# PowerSupply.net
KiCad netlist of a schematic drawn in Altium Designer
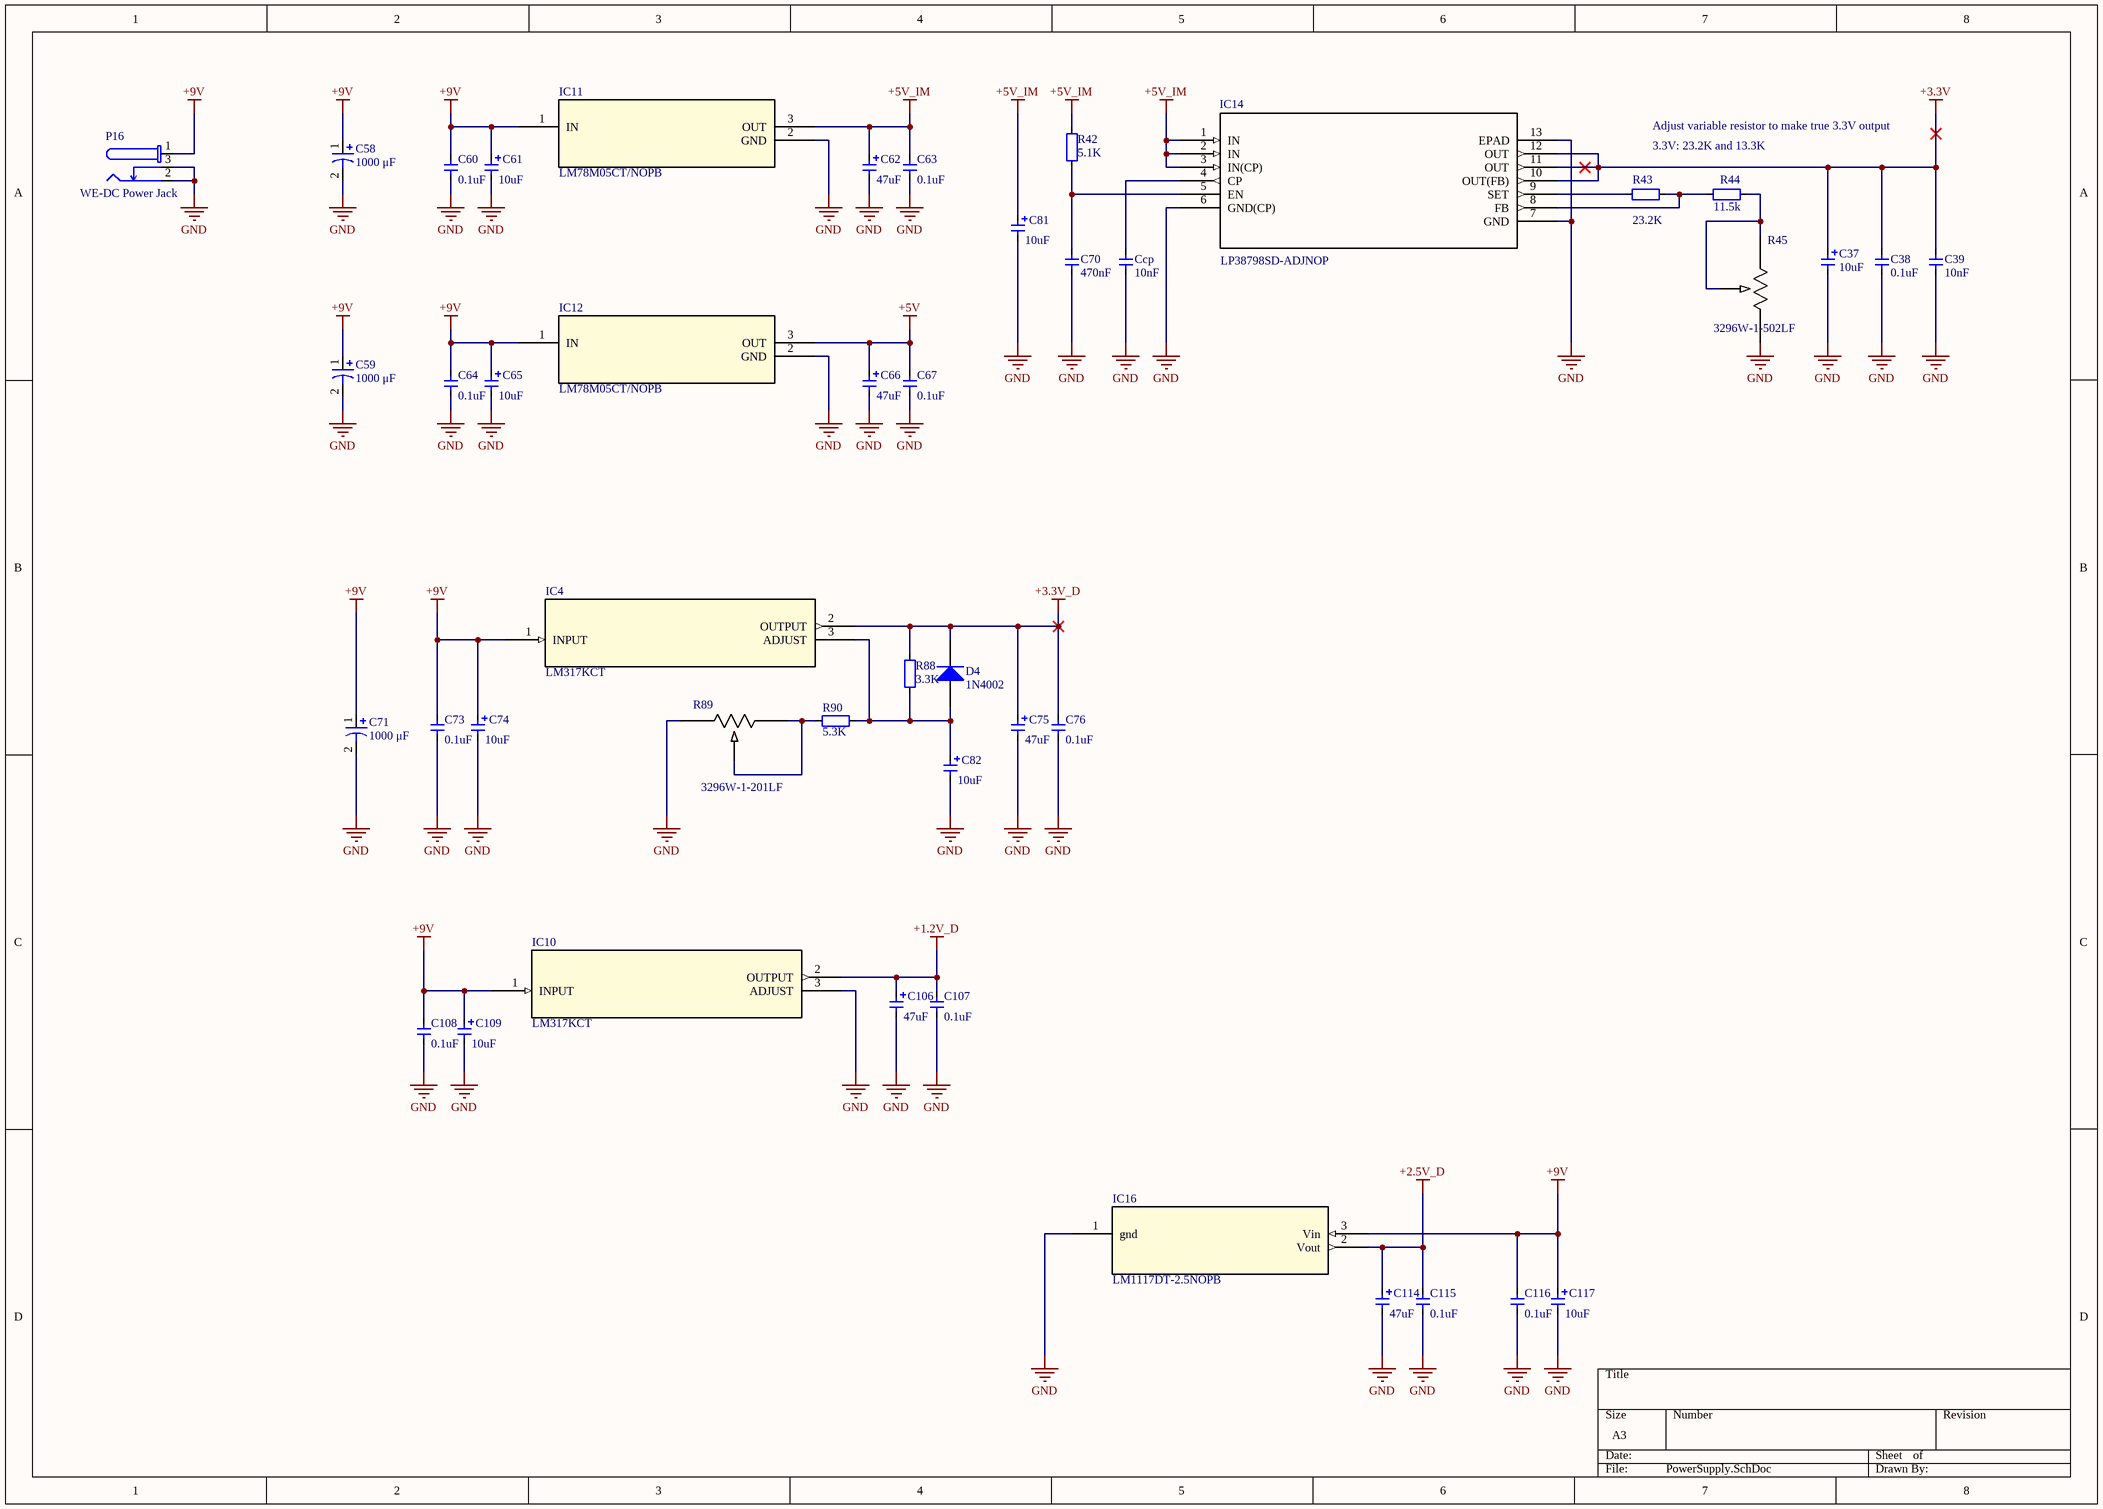
[diagram p0: PowerSupply.SchDoc]

(export (version "E")
  (design (tool "Eeschema 10.0.6"))
  (components
    (comp (ref "C37")
      (value "10uF")
      (footprint "PCB_PassiveCap:CAP_TAN_A1206")
      (description "Capacitor")
      (fields (field (name "Comment") "Cap_Tan_1206"))
      (libsource (lib "SCH_Passive") (part "Cap_Tan_1206"))
    )
    (comp (ref "C38")
      (value "0.1uF")
      (footprint "PCB_PassiveCap:CAP_0603")
      (description "Capacitor")
      (fields (field (name "Comment") "Cap_0603"))
      (libsource (lib "SCH_Passive") (part "Cap_0603"))
    )
    (comp (ref "C39")
      (value "10nF")
      (footprint "PCB_PassiveCap:CAP_0603")
      (description "Capacitor")
      (fields (field (name "Comment") "Cap_0603"))
      (libsource (lib "SCH_Passive") (part "Cap_0603"))
    )
    (comp (ref "C58")
      (value "1000 μF")
      (footprint "WCAP-ATUL 5x11x2x0.5")
      (description "WCAP-ATUL Aluminum Electrolytic Capacitors , 100 μF; + / - 20%; 10 V , 5 x 11")
      (fields
        (field (name "MANUFACTURER") "Wurth Elektronik")
        (field (name "PARTNO") "860040272001")
        (field (name "E-MAIL") "libraries@we-online.com")
        (field (name "CREATED BY") "Karrer Zheng")
      )
      (libsource (lib "WCAP-ATUL_rev15a") (part "WCAP-ATUL 5x11x2x0.5 860040272001"))
    )
    (comp (ref "C59")
      (value "1000 μF")
      (footprint "WCAP-ATUL 5x11x2x0.5")
      (description "WCAP-ATUL Aluminum Electrolytic Capacitors , 100 μF; + / - 20%; 10 V , 5 x 11")
      (fields
        (field (name "MANUFACTURER") "Wurth Elektronik")
        (field (name "PARTNO") "860040272001")
        (field (name "E-MAIL") "libraries@we-online.com")
        (field (name "CREATED BY") "Karrer Zheng")
      )
      (libsource (lib "WCAP-ATUL_rev15a") (part "WCAP-ATUL 5x11x2x0.5 860040272001"))
    )
    (comp (ref "C60")
      (value "0.1uF")
      (footprint "PCB_PassiveCap:CAP_0603")
      (description "Capacitor")
      (fields (field (name "Comment") "Cap_0603"))
      (libsource (lib "SCH_Passive") (part "Cap_0603"))
    )
    (comp (ref "C61")
      (value "10uF")
      (footprint "PCB_PassiveCap:CAP_TAN_A1206")
      (description "Capacitor")
      (fields (field (name "Comment") "Cap_Tan_1206"))
      (libsource (lib "SCH_Passive") (part "Cap_Tan_1206"))
    )
    (comp (ref "C62")
      (value "47uF")
      (footprint "PCB_PassiveCap:CAP_TAN_A1206")
      (description "Capacitor")
      (fields (field (name "Comment") "Cap_Tan_1206"))
      (libsource (lib "SCH_Passive") (part "Cap_Tan_1206"))
    )
    (comp (ref "C63")
      (value "0.1uF")
      (footprint "PCB_PassiveCap:CAP_0603")
      (description "Capacitor")
      (fields (field (name "Comment") "Cap_0603"))
      (libsource (lib "SCH_Passive") (part "Cap_0603"))
    )
    (comp (ref "C64")
      (value "0.1uF")
      (footprint "PCB_PassiveCap:CAP_0603")
      (description "Capacitor")
      (fields (field (name "Comment") "Cap_0603"))
      (libsource (lib "SCH_Passive") (part "Cap_0603"))
    )
    (comp (ref "C65")
      (value "10uF")
      (footprint "PCB_PassiveCap:CAP_TAN_A1206")
      (description "Capacitor")
      (fields (field (name "Comment") "Cap_Tan_1206"))
      (libsource (lib "SCH_Passive") (part "Cap_Tan_1206"))
    )
    (comp (ref "C66")
      (value "47uF")
      (footprint "PCB_PassiveCap:CAP_TAN_A1206")
      (description "Capacitor")
      (fields (field (name "Comment") "Cap_Tan_1206"))
      (libsource (lib "SCH_Passive") (part "Cap_Tan_1206"))
    )
    (comp (ref "C67")
      (value "0.1uF")
      (footprint "PCB_PassiveCap:CAP_0603")
      (description "Capacitor")
      (fields (field (name "Comment") "Cap_0603"))
      (libsource (lib "SCH_Passive") (part "Cap_0603"))
    )
    (comp (ref "C70")
      (value "470nF")
      (footprint "PCB_PassiveCap:CAP_0603")
      (description "Capacitor")
      (fields (field (name "Comment") "Cap_0603"))
      (libsource (lib "SCH_Passive") (part "Cap_0603"))
    )
    (comp (ref "C71")
      (value "1000 μF")
      (footprint "WCAP-ATUL 5x11x2x0.5")
      (description "WCAP-ATUL Aluminum Electrolytic Capacitors , 100 μF; + / - 20%; 10 V , 5 x 11")
      (fields
        (field (name "MANUFACTURER") "Wurth Elektronik")
        (field (name "PARTNO") "860040272001")
        (field (name "E-MAIL") "libraries@we-online.com")
        (field (name "CREATED BY") "Karrer Zheng")
      )
      (libsource (lib "WCAP-ATUL_rev15a") (part "WCAP-ATUL 5x11x2x0.5 860040272001"))
    )
    (comp (ref "C73")
      (value "0.1uF")
      (footprint "PCB_PassiveCap:CAP_0603")
      (description "Capacitor")
      (fields (field (name "Comment") "Cap_0603"))
      (libsource (lib "SCH_Passive") (part "Cap_0603"))
    )
    (comp (ref "C74")
      (value "10uF")
      (footprint "PCB_PassiveCap:CAP_TAN_A1206")
      (description "Capacitor")
      (fields (field (name "Comment") "Cap_Tan_1206"))
      (libsource (lib "SCH_Passive") (part "Cap_Tan_1206"))
    )
    (comp (ref "C75")
      (value "47uF")
      (footprint "PCB_PassiveCap:CAP_TAN_A1206")
      (description "Capacitor")
      (fields (field (name "Comment") "Cap_Tan_1206"))
      (libsource (lib "SCH_Passive") (part "Cap_Tan_1206"))
    )
    (comp (ref "C76")
      (value "0.1uF")
      (footprint "PCB_PassiveCap:CAP_0603")
      (description "Capacitor")
      (fields (field (name "Comment") "Cap_0603"))
      (libsource (lib "SCH_Passive") (part "Cap_0603"))
    )
    (comp (ref "C81")
      (value "10uF")
      (footprint "PCB_PassiveCap:CAP_TAN_A1206")
      (description "Capacitor")
      (fields (field (name "Comment") "Cap_Tan_1206"))
      (libsource (lib "SCH_Passive") (part "Cap_Tan_1206"))
    )
    (comp (ref "C82")
      (value "10uF")
      (footprint "PCB_PassiveCap:CAP_TAN_A1206")
      (description "Capacitor")
      (fields (field (name "Comment") "Cap_Tan_1206"))
      (libsource (lib "SCH_Passive") (part "Cap_Tan_1206"))
    )
    (comp (ref "C106")
      (value "47uF")
      (footprint "PCB_PassiveCap:CAP_TAN_A1206")
      (description "Capacitor")
      (fields (field (name "Comment") "Cap_Tan_1206"))
      (libsource (lib "SCH_Passive") (part "Cap_Tan_1206"))
    )
    (comp (ref "C107")
      (value "0.1uF")
      (footprint "PCB_PassiveCap:CAP_0603")
      (description "Capacitor")
      (fields (field (name "Comment") "Cap_0603"))
      (libsource (lib "SCH_Passive") (part "Cap_0603"))
    )
    (comp (ref "C108")
      (value "0.1uF")
      (footprint "PCB_PassiveCap:CAP_0603")
      (description "Capacitor")
      (fields (field (name "Comment") "Cap_0603"))
      (libsource (lib "SCH_Passive") (part "Cap_0603"))
    )
    (comp (ref "C109")
      (value "10uF")
      (footprint "PCB_PassiveCap:CAP_TAN_A1206")
      (description "Capacitor")
      (fields (field (name "Comment") "Cap_Tan_1206"))
      (libsource (lib "SCH_Passive") (part "Cap_Tan_1206"))
    )
    (comp (ref "C114")
      (value "47uF")
      (footprint "PCB_PassiveCap:CAP_TAN_A1206")
      (description "Capacitor")
      (fields (field (name "Comment") "Cap_Tan_1206"))
      (libsource (lib "SCH_Passive") (part "Cap_Tan_1206"))
    )
    (comp (ref "C115")
      (value "0.1uF")
      (footprint "PCB_PassiveCap:CAP_0603")
      (description "Capacitor")
      (fields (field (name "Comment") "Cap_0603"))
      (libsource (lib "SCH_Passive") (part "Cap_0603"))
    )
    (comp (ref "C116")
      (value "0.1uF")
      (footprint "PCB_PassiveCap:CAP_0603")
      (description "Capacitor")
      (fields (field (name "Comment") "Cap_0603"))
      (libsource (lib "SCH_Passive") (part "Cap_0603"))
    )
    (comp (ref "C117")
      (value "10uF")
      (footprint "PCB_PassiveCap:CAP_TAN_A1206")
      (description "Capacitor")
      (fields (field (name "Comment") "Cap_Tan_1206"))
      (libsource (lib "SCH_Passive") (part "Cap_Tan_1206"))
    )
    (comp (ref "Ccp")
      (value "10nF")
      (footprint "PCB_PassiveCap:CAP_0603")
      (description "Capacitor")
      (fields (field (name "Comment") "Cap_0603"))
      (libsource (lib "SCH_Passive") (part "Cap_0603"))
    )
    (comp (ref "D4")
      (value "1N4002")
      (footprint "DO-41")
      (description "1 Amp General Purpose Rectifier")
      (fields (field (name "PUBLISHER") "Altium Limited"))
      (libsource (lib "Miscellaneous Devices") (part "Diode 1N4002"))
    )
    (comp (ref "IC4")
      (value "LM317KCT")
      (footprint "KC3")
      (description "Imported")
      (fields
        (field (name "MANUFACTURER") "Texas Instruments")
        (field (name "GENERIC_PART_NUMBER") "LM317")
        (field (name "COPYRIGHT") "Copyright (C) 2015 Accelerated Designs. All rights reserved")
      )
      (libsource (lib "LM317") (part "LM317KCT"))
    )
    (comp (ref "IC10")
      (value "LM317KCT")
      (footprint "KC3")
      (description "Imported")
      (fields
        (field (name "MANUFACTURER") "Texas Instruments")
        (field (name "GENERIC_PART_NUMBER") "LM317")
        (field (name "COPYRIGHT") "Copyright (C) 2015 Accelerated Designs. All rights reserved")
      )
      (libsource (lib "LM317") (part "LM317KCT"))
    )
    (comp (ref "IC11")
      (value "LM78M05CT/NOPB")
      (footprint "T03B")
      (description "Imported")
      (fields
        (field (name "MANUFACTURER_PART_NUMBER") "lm78m05ct")
        (field (name "COPYRIGHT") "Copyright (C) 2015 Accelerated Designs. All rights reserved")
      )
      (libsource (lib "LM7805") (part "LM78M05CT/NOPB"))
    )
    (comp (ref "IC12")
      (value "LM78M05CT/NOPB")
      (footprint "T03B")
      (description "Imported")
      (fields
        (field (name "MANUFACTURER_PART_NUMBER") "lm78m05ct")
        (field (name "COPYRIGHT") "Copyright (C) 2015 Accelerated Designs. All rights reserved")
      )
      (libsource (lib "LM7805") (part "LM78M05CT/NOPB"))
    )
    (comp (ref "IC14")
      (value "LP38798SD-ADJNOP")
      (footprint "DNT12")
      (description "Imported")
      (fields
        (field (name "MANUFACTURER_PART_NUMBER") "lp38798sd-adj/nopb")
        (field (name "COPYRIGHT") "Copyright (C) 2015 Accelerated Designs. All rights reserved")
      )
      (libsource (lib "LP38798") (part "LP38798SD-ADJNOP"))
    )
    (comp (ref "IC16")
      (value "LM1117DT-2.5NOPB")
      (footprint "TD03B")
      (description "Imported")
      (fields
        (field (name "MANUFACTURER_PART_NUMBER") "LM1117DT-18")
        (field (name "COPYRIGHT") "Copyright (C) 2015 Accelerated Designs. All rights reserved")
      )
      (libsource (lib "LM1117DT-1") (part "LM1117DT-1_8NOPB"))
    )
    (comp (ref "P16")
      (value "WE-DC Power Jack")
      (footprint "694106106102")
      (description "WR-DC_DC Power Jack_Right Angled_SMT")
      (fields
        (field (name "MANUFACTURER") "WЁ№rth Elektronik eiSos GmbH")
        (field (name "PARTNO") "694106106102")
        (field (name "CREATED BY") "Karrer Zheng")
      )
      (libsource (lib "DC_Power_Jack_rev15b") (part "WE-DC Power Jack 694106106102"))
    )
    (comp (ref "R42")
      (value "5.1K")
      (footprint "PCB_PassiveRes:RES_0603")
      (description "Resistor")
      (fields (field (name "Comment") "Res_0603"))
      (libsource (lib "") (part "Res_0603_3"))
    )
    (comp (ref "R43")
      (value "23.2K")
      (footprint "PCB_PassiveRes:RES_0603")
      (description "Resistor")
      (fields (field (name "Comment") "Res_0603"))
      (libsource (lib "") (part "Res_0603_2"))
    )
    (comp (ref "R44")
      (value "11.5k")
      (footprint "PCB_PassiveRes:RES_0603")
      (description "Resistor")
      (fields (field (name "Comment") "Res_0603"))
      (libsource (lib "") (part "Res_0603_1"))
    )
    (comp (ref "R45")
      (value "3296W-1-502LF")
      (footprint "POT_3296W")
      (description "Imported")
      (fields
        (field (name "MANUFACTURER_PART_NUMBER") "3296W-1-503LF")
        (field (name "TOLERANCE") "10%")
        (field (name "COPYRIGHT") "Copyright (C) 2015 Accelerated Designs. All rights reserved")
      )
      (libsource (lib "ResVar") (part "3296W-1-503LF"))
    )
    (comp (ref "R88")
      (value "3.3K")
      (footprint "PCB_PassiveRes:RES_0603")
      (description "Resistor")
      (fields (field (name "Comment") "Res_0603"))
      (libsource (lib "SCH_Passive") (part "Res_0603"))
    )
    (comp (ref "R89")
      (value "3296W-1-201LF")
      (footprint "POT_3296W")
      (description "Imported")
      (fields
        (field (name "MANUFACTURER_PART_NUMBER") "3296W-1-503LF")
        (field (name "TOLERANCE") "10%")
        (field (name "COPYRIGHT") "Copyright (C) 2015 Accelerated Designs. All rights reserved")
      )
      (libsource (lib "ResVar") (part "3296W-1-503LF"))
    )
    (comp (ref "R90")
      (value "5.3K")
      (footprint "PCB_PassiveRes:RES_0603")
      (description "Resistor")
      (fields (field (name "Comment") "Res_0603"))
      (libsource (lib "") (part "Res_0603_2"))
    )
  )
  (nets
    (net (code "1") (name "+1.2V_D") (class "Default")
      (node (ref "C106") (pin "1") (pinfunction "1_1") (pintype "passive"))
      (node (ref "C107") (pin "2") (pinfunction "2_2") (pintype "passive"))
      (node (ref "IC10") (pin "2") (pinfunction "OUTPUT_2") (pintype "output"))
    )
    (net (code "2") (name "+2.5V_D") (class "Default")
      (node (ref "C114") (pin "1") (pinfunction "1_1") (pintype "passive"))
      (node (ref "C115") (pin "2") (pinfunction "2_2") (pintype "passive"))
      (node (ref "IC16") (pin "2") (pinfunction "Vout_2") (pintype "output"))
    )
    (net (code "3") (name "+3.3V") (class "Default")
      (node (ref "C37") (pin "1") (pinfunction "1_1") (pintype "passive"))
      (node (ref "C38") (pin "2") (pinfunction "2_2") (pintype "passive"))
      (node (ref "C39") (pin "2") (pinfunction "2_2") (pintype "passive"))
      (node (ref "IC14") (pin "10") (pinfunction "OUT(FB)_10") (pintype "output"))
      (node (ref "IC14") (pin "11") (pinfunction "OUT_11") (pintype "output"))
      (node (ref "IC14") (pin "12") (pinfunction "OUT_12") (pintype "output"))
    )
    (net (code "4") (name "+3.3V_D") (class "Default")
      (node (ref "C75") (pin "1") (pinfunction "1_1") (pintype "passive"))
      (node (ref "C76") (pin "2") (pinfunction "2_2") (pintype "passive"))
      (node (ref "D4") (pin "2") (pinfunction "K_2") (pintype "passive"))
      (node (ref "IC4") (pin "2") (pinfunction "OUTPUT_2") (pintype "output"))
      (node (ref "R88") (pin "2") (pinfunction "2_2") (pintype "passive"))
    )
    (net (code "5") (name "+5V") (class "Default")
      (node (ref "C66") (pin "1") (pinfunction "1_1") (pintype "passive"))
      (node (ref "C67") (pin "2") (pinfunction "2_2") (pintype "passive"))
      (node (ref "IC12") (pin "3") (pinfunction "OUT_3") (pintype "power_in"))
    )
    (net (code "6") (name "+5V_IM") (class "Default")
      (node (ref "C62") (pin "1") (pinfunction "1_1") (pintype "passive"))
      (node (ref "C63") (pin "2") (pinfunction "2_2") (pintype "passive"))
      (node (ref "C81") (pin "1") (pinfunction "1_1") (pintype "passive"))
      (node (ref "IC11") (pin "3") (pinfunction "OUT_3") (pintype "power_in"))
      (node (ref "IC14") (pin "1") (pinfunction "IN_1") (pintype "input"))
      (node (ref "IC14") (pin "2") (pinfunction "IN_2") (pintype "input"))
      (node (ref "IC14") (pin "3") (pinfunction "IN(CP)_3") (pintype "input"))
      (node (ref "R42") (pin "1") (pinfunction "1_1") (pintype "passive"))
    )
    (net (code "7") (name "+9V") (class "Default")
      (node (ref "C108") (pin "2") (pinfunction "2_2") (pintype "passive"))
      (node (ref "C109") (pin "1") (pinfunction "1_1") (pintype "passive"))
      (node (ref "C116") (pin "2") (pinfunction "2_2") (pintype "passive"))
      (node (ref "C117") (pin "1") (pinfunction "1_1") (pintype "passive"))
      (node (ref "C58") (pin "1") (pinfunction "1_1") (pintype "passive"))
      (node (ref "C59") (pin "1") (pinfunction "1_1") (pintype "passive"))
      (node (ref "C60") (pin "2") (pinfunction "2_2") (pintype "passive"))
      (node (ref "C61") (pin "1") (pinfunction "1_1") (pintype "passive"))
      (node (ref "C64") (pin "2") (pinfunction "2_2") (pintype "passive"))
      (node (ref "C65") (pin "1") (pinfunction "1_1") (pintype "passive"))
      (node (ref "C71") (pin "1") (pinfunction "1_1") (pintype "passive"))
      (node (ref "C73") (pin "2") (pinfunction "2_2") (pintype "passive"))
      (node (ref "C74") (pin "1") (pinfunction "1_1") (pintype "passive"))
      (node (ref "IC10") (pin "1") (pinfunction "INPUT_1") (pintype "input"))
      (node (ref "IC11") (pin "1") (pinfunction "IN_1") (pintype "power_in"))
      (node (ref "IC12") (pin "1") (pinfunction "IN_1") (pintype "power_in"))
      (node (ref "IC16") (pin "3") (pinfunction "Vin_3") (pintype "input"))
      (node (ref "IC4") (pin "1") (pinfunction "INPUT_1") (pintype "input"))
      (node (ref "P16") (pin "1") (pinfunction "1_1") (pintype "power_in"))
    )
    (net (code "8") (name "GND") (class "Default")
      (node (ref "C106") (pin "2") (pinfunction "2_2") (pintype "passive"))
      (node (ref "C107") (pin "1") (pinfunction "1_1") (pintype "passive"))
      (node (ref "C108") (pin "1") (pinfunction "1_1") (pintype "passive"))
      (node (ref "C109") (pin "2") (pinfunction "2_2") (pintype "passive"))
      (node (ref "C114") (pin "2") (pinfunction "2_2") (pintype "passive"))
      (node (ref "C115") (pin "1") (pinfunction "1_1") (pintype "passive"))
      (node (ref "C116") (pin "1") (pinfunction "1_1") (pintype "passive"))
      (node (ref "C117") (pin "2") (pinfunction "2_2") (pintype "passive"))
      (node (ref "C37") (pin "2") (pinfunction "2_2") (pintype "passive"))
      (node (ref "C38") (pin "1") (pinfunction "1_1") (pintype "passive"))
      (node (ref "C39") (pin "1") (pinfunction "1_1") (pintype "passive"))
      (node (ref "C58") (pin "2") (pinfunction "2_2") (pintype "passive"))
      (node (ref "C59") (pin "2") (pinfunction "2_2") (pintype "passive"))
      (node (ref "C60") (pin "1") (pinfunction "1_1") (pintype "passive"))
      (node (ref "C61") (pin "2") (pinfunction "2_2") (pintype "passive"))
      (node (ref "C62") (pin "2") (pinfunction "2_2") (pintype "passive"))
      (node (ref "C63") (pin "1") (pinfunction "1_1") (pintype "passive"))
      (node (ref "C64") (pin "1") (pinfunction "1_1") (pintype "passive"))
      (node (ref "C65") (pin "2") (pinfunction "2_2") (pintype "passive"))
      (node (ref "C66") (pin "2") (pinfunction "2_2") (pintype "passive"))
      (node (ref "C67") (pin "1") (pinfunction "1_1") (pintype "passive"))
      (node (ref "C70") (pin "1") (pinfunction "1_1") (pintype "passive"))
      (node (ref "C71") (pin "2") (pinfunction "2_2") (pintype "passive"))
      (node (ref "C73") (pin "1") (pinfunction "1_1") (pintype "passive"))
      (node (ref "C74") (pin "2") (pinfunction "2_2") (pintype "passive"))
      (node (ref "C75") (pin "2") (pinfunction "2_2") (pintype "passive"))
      (node (ref "C76") (pin "1") (pinfunction "1_1") (pintype "passive"))
      (node (ref "C81") (pin "2") (pinfunction "2_2") (pintype "passive"))
      (node (ref "C82") (pin "2") (pinfunction "2_2") (pintype "passive"))
      (node (ref "Ccp") (pin "1") (pinfunction "1_1") (pintype "passive"))
      (node (ref "IC10") (pin "3") (pinfunction "ADJUST_3") (pintype "passive"))
      (node (ref "IC11") (pin "2") (pinfunction "GND_2") (pintype "power_in"))
      (node (ref "IC12") (pin "2") (pinfunction "GND_2") (pintype "power_in"))
      (node (ref "IC14") (pin "13") (pinfunction "EPAD_13") (pintype "passive"))
      (node (ref "IC14") (pin "6") (pinfunction "GND(CP)_6") (pintype "power_in"))
      (node (ref "IC14") (pin "7") (pinfunction "GND_7") (pintype "power_in"))
      (node (ref "IC16") (pin "1") (pinfunction "gnd_1") (pintype "power_in"))
      (node (ref "P16") (pin "2") (pinfunction "2_2") (pintype "power_in"))
      (node (ref "P16") (pin "3") (pinfunction "3_3") (pintype "power_in"))
      (node (ref "R45") (pin "1") (pinfunction "1_1") (pintype "passive"))
      (node (ref "R89") (pin "3") (pinfunction "3_3") (pintype "passive"))
    )
    (net (code "9") (name "Net-(D4-A)") (class "Default")
      (node (ref "C82") (pin "1") (pinfunction "1_1") (pintype "passive"))
      (node (ref "D4") (pin "1") (pinfunction "A_1") (pintype "passive"))
      (node (ref "IC4") (pin "3") (pinfunction "ADJUST_3") (pintype "passive"))
      (node (ref "R88") (pin "1") (pinfunction "1_1") (pintype "passive"))
      (node (ref "R90") (pin "2") (pinfunction "2_2") (pintype "passive"))
    )
    (net (code "10") (name "Net-(IC14-CP)") (class "Default")
      (node (ref "Ccp") (pin "2") (pinfunction "2_2") (pintype "passive"))
      (node (ref "IC14") (pin "4") (pinfunction "CP_4") (pintype "output"))
    )
    (net (code "11") (name "Net-(IC14-EN)") (class "Default")
      (node (ref "C70") (pin "2") (pinfunction "2_2") (pintype "passive"))
      (node (ref "IC14") (pin "5") (pinfunction "EN_5") (pintype "passive"))
      (node (ref "R42") (pin "2") (pinfunction "2_2") (pintype "passive"))
    )
    (net (code "12") (name "Net-(IC14-FB)") (class "Default")
      (node (ref "IC14") (pin "8") (pinfunction "FB_8") (pintype "output"))
      (node (ref "R43") (pin "2") (pinfunction "2_2") (pintype "passive"))
      (node (ref "R44") (pin "2") (pinfunction "2_2") (pintype "passive"))
    )
    (net (code "13") (name "Net-(IC14-SET)") (class "Default")
      (node (ref "IC14") (pin "9") (pinfunction "SET_9") (pintype "output"))
      (node (ref "R43") (pin "1") (pinfunction "1_1") (pintype "passive"))
    )
    (net (code "14") (name "Net-(R44-Pad1)") (class "Default")
      (node (ref "R44") (pin "1") (pinfunction "1_1") (pintype "passive"))
      (node (ref "R45") (pin "2") (pinfunction "2_2") (pintype "passive"))
      (node (ref "R45") (pin "3") (pinfunction "3_3") (pintype "passive"))
    )
    (net (code "15") (name "Net-(R89-Pad1)") (class "Default")
      (node (ref "R89") (pin "1") (pinfunction "1_1") (pintype "passive"))
      (node (ref "R89") (pin "2") (pinfunction "2_2") (pintype "passive"))
      (node (ref "R90") (pin "1") (pinfunction "1_1") (pintype "passive"))
    )
  )
)
